# Tape_V2.net
KiCad netlist of a schematic drawn in EAGLE
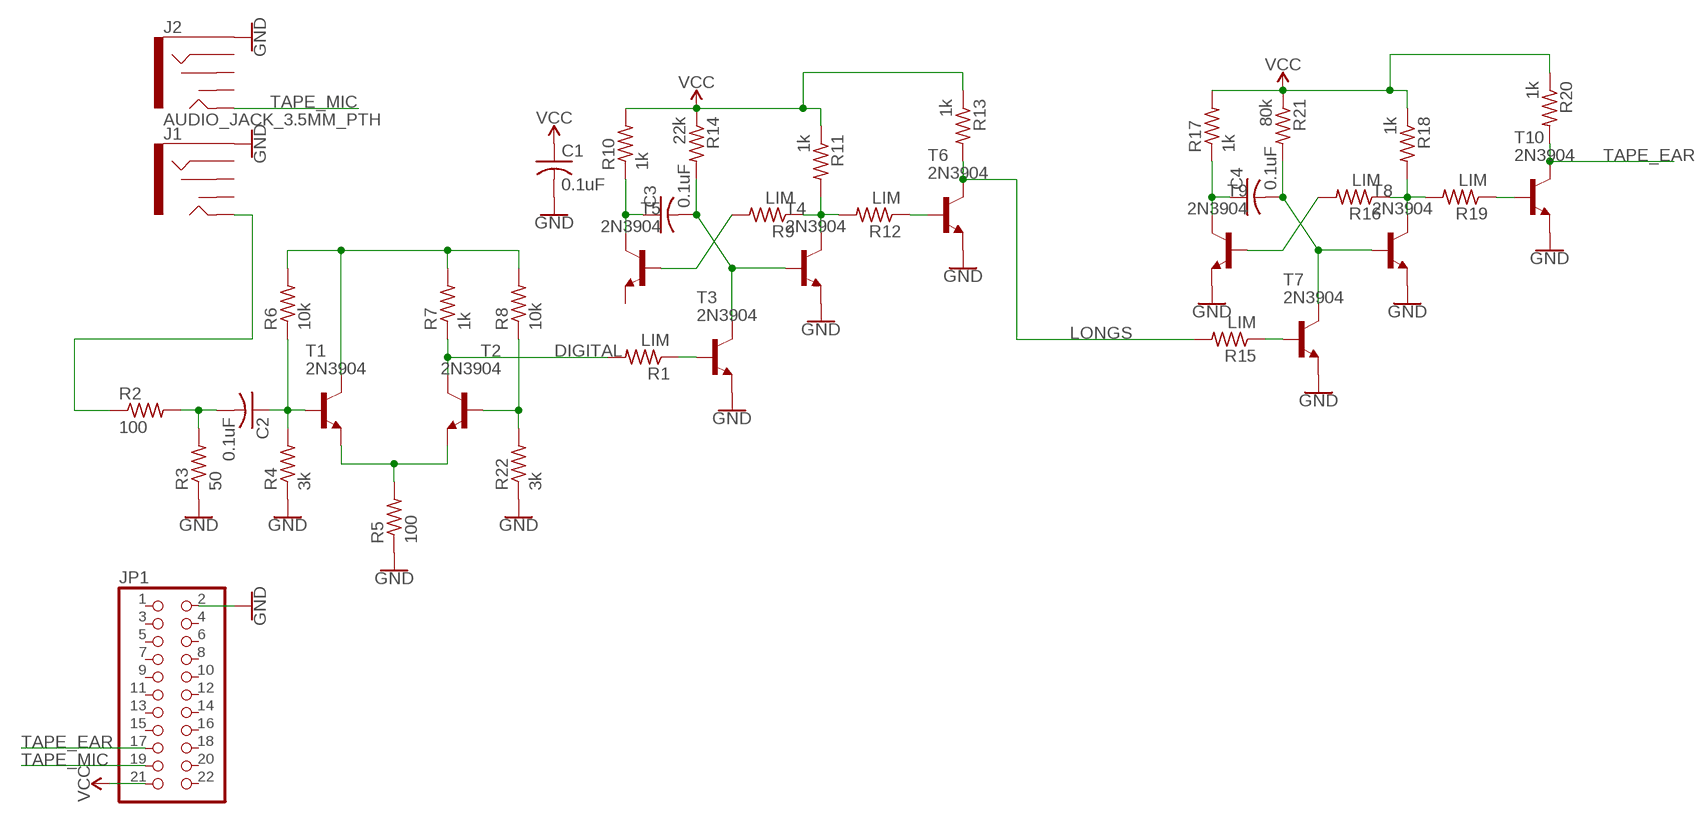
[diagram p0: schematic, sheet 1]

(export (version "E")
  (design (tool "Eeschema 10.0.6"))
  (components
    (comp (ref "C1")
      (value "0.1uF")
      (footprint "eagle-import:C025-030X050")
      (libsource (lib "eagle-import") (part "C-US025-030X050"))
    )
    (comp (ref "C2")
      (value "0.1uF")
      (footprint "eagle-import:C025-030X050")
      (libsource (lib "eagle-import") (part "C-US025-030X050"))
    )
    (comp (ref "C3")
      (value "0.1uF")
      (footprint "eagle-import:C025-030X050")
      (libsource (lib "eagle-import") (part "C-US025-030X050"))
    )
    (comp (ref "C4")
      (value "0.1uF")
      (footprint "eagle-import:C025-030X050")
      (libsource (lib "eagle-import") (part "C-US025-030X050"))
    )
    (comp (ref "J1")
      (value "AUDIO_JACK_3.5MM_PTH")
      (footprint "eagle-import:AUDIO-JACK")
      (libsource (lib "eagle-import") (part "AUDIO_JACK_3.5MM_PTH"))
    )
    (comp (ref "J2")
      (value "AUDIO_JACK_3.5MM_PTH")
      (footprint "eagle-import:AUDIO-JACK")
      (libsource (lib "eagle-import") (part "AUDIO_JACK_3.5MM_PTH"))
    )
    (comp (ref "JP1")
      (value "PINHD-2X11/90")
      (footprint "eagle-import:2X11_90")
      (libsource (lib "eagle-import") (part "PINHD-2X11/90"))
    )
    (comp (ref "R1")
      (value "LIM")
      (footprint "eagle-import:0204_7")
      (libsource (lib "eagle-import") (part "R-US_0204/7"))
    )
    (comp (ref "R2")
      (value "100")
      (footprint "eagle-import:0204_7")
      (libsource (lib "eagle-import") (part "R-US_0204/7"))
    )
    (comp (ref "R3")
      (value "50")
      (footprint "eagle-import:0204_7")
      (libsource (lib "eagle-import") (part "R-US_0204/7"))
    )
    (comp (ref "R4")
      (value "3k")
      (footprint "eagle-import:0204_7")
      (libsource (lib "eagle-import") (part "R-US_0204/7"))
    )
    (comp (ref "R5")
      (value "100")
      (footprint "eagle-import:0204_7")
      (libsource (lib "eagle-import") (part "R-US_0204/7"))
    )
    (comp (ref "R6")
      (value "10k")
      (footprint "eagle-import:0204_7")
      (libsource (lib "eagle-import") (part "R-US_0204/7"))
    )
    (comp (ref "R7")
      (value "1k")
      (footprint "eagle-import:0204_7")
      (libsource (lib "eagle-import") (part "R-US_0204/7"))
    )
    (comp (ref "R8")
      (value "10k")
      (footprint "eagle-import:0204_7")
      (libsource (lib "eagle-import") (part "R-US_0204/7"))
    )
    (comp (ref "R9")
      (value "LIM")
      (footprint "eagle-import:0204_7")
      (libsource (lib "eagle-import") (part "R-US_0204/7"))
    )
    (comp (ref "R10")
      (value "1k")
      (footprint "eagle-import:0204_7")
      (libsource (lib "eagle-import") (part "R-US_0204/7"))
    )
    (comp (ref "R11")
      (value "1k")
      (footprint "eagle-import:0204_7")
      (libsource (lib "eagle-import") (part "R-US_0204/7"))
    )
    (comp (ref "R12")
      (value "LIM")
      (footprint "eagle-import:0204_7")
      (libsource (lib "eagle-import") (part "R-US_0204/7"))
    )
    (comp (ref "R13")
      (value "1k")
      (footprint "eagle-import:0204_7")
      (libsource (lib "eagle-import") (part "R-US_0204/7"))
    )
    (comp (ref "R14")
      (value "22k")
      (footprint "eagle-import:0204_7")
      (libsource (lib "eagle-import") (part "R-US_0204/7"))
    )
    (comp (ref "R15")
      (value "LIM")
      (footprint "eagle-import:0204_7")
      (libsource (lib "eagle-import") (part "R-US_0204/7"))
    )
    (comp (ref "R16")
      (value "LIM")
      (footprint "eagle-import:0204_7")
      (libsource (lib "eagle-import") (part "R-US_0204/7"))
    )
    (comp (ref "R17")
      (value "1k")
      (footprint "eagle-import:0204_7")
      (libsource (lib "eagle-import") (part "R-US_0204/7"))
    )
    (comp (ref "R18")
      (value "1k")
      (footprint "eagle-import:0204_7")
      (libsource (lib "eagle-import") (part "R-US_0204/7"))
    )
    (comp (ref "R19")
      (value "LIM")
      (footprint "eagle-import:0204_7")
      (libsource (lib "eagle-import") (part "R-US_0204/7"))
    )
    (comp (ref "R20")
      (value "1k")
      (footprint "eagle-import:0204_7")
      (libsource (lib "eagle-import") (part "R-US_0204/7"))
    )
    (comp (ref "R21")
      (value "80k")
      (footprint "eagle-import:0204_7")
      (libsource (lib "eagle-import") (part "R-US_0204/7"))
    )
    (comp (ref "R22")
      (value "3k")
      (footprint "eagle-import:0204_7")
      (libsource (lib "eagle-import") (part "R-US_0204/7"))
    )
    (comp (ref "T1")
      (value "2N3904")
      (footprint "eagle-import:TO92")
      (libsource (lib "eagle-import") (part "2N3904"))
    )
    (comp (ref "T2")
      (value "2N3904")
      (footprint "eagle-import:TO92")
      (libsource (lib "eagle-import") (part "2N3904"))
    )
    (comp (ref "T3")
      (value "2N3904")
      (footprint "eagle-import:TO92")
      (libsource (lib "eagle-import") (part "2N3904"))
    )
    (comp (ref "T4")
      (value "2N3904")
      (footprint "eagle-import:TO92")
      (libsource (lib "eagle-import") (part "2N3904"))
    )
    (comp (ref "T5")
      (value "2N3904")
      (footprint "eagle-import:TO92")
      (libsource (lib "eagle-import") (part "2N3904"))
    )
    (comp (ref "T6")
      (value "2N3904")
      (footprint "eagle-import:TO92")
      (libsource (lib "eagle-import") (part "2N3904"))
    )
    (comp (ref "T7")
      (value "2N3904")
      (footprint "eagle-import:TO92")
      (libsource (lib "eagle-import") (part "2N3904"))
    )
    (comp (ref "T8")
      (value "2N3904")
      (footprint "eagle-import:TO92")
      (libsource (lib "eagle-import") (part "2N3904"))
    )
    (comp (ref "T9")
      (value "2N3904")
      (footprint "eagle-import:TO92")
      (libsource (lib "eagle-import") (part "2N3904"))
    )
    (comp (ref "T10")
      (value "2N3904")
      (footprint "eagle-import:TO92")
      (libsource (lib "eagle-import") (part "2N3904"))
    )
  )
  (nets
    (net (code "1") (name "/DIGITAL") (class "Default")
      (node (ref "R1") (pin "2") (pinfunction "2_2") (pintype "passive"))
      (node (ref "R7") (pin "1") (pinfunction "1_1") (pintype "passive"))
      (node (ref "T2") (pin "1") (pinfunction "C_1") (pintype "passive"))
    )
    (net (code "2") (name "/LONGS") (class "Default")
      (node (ref "R13") (pin "2") (pinfunction "2_2") (pintype "passive"))
      (node (ref "R15") (pin "2") (pinfunction "2_2") (pintype "passive"))
      (node (ref "T6") (pin "1") (pinfunction "C_1") (pintype "passive"))
    )
    (net (code "3") (name "/TAPE_EAR") (class "Default")
      (node (ref "JP1") (pin "17") (pinfunction "17_17") (pintype "passive"))
      (node (ref "R20") (pin "2") (pinfunction "2_2") (pintype "passive"))
      (node (ref "T10") (pin "1") (pinfunction "C_1") (pintype "passive"))
    )
    (net (code "4") (name "/TAPE_MIC") (class "Default")
      (node (ref "J2") (pin "TIP") (pinfunction "TIP_TIP") (pintype "bidirectional"))
      (node (ref "JP1") (pin "19") (pinfunction "19_19") (pintype "passive"))
    )
    (net (code "5") (name "GND") (class "Default")
      (node (ref "C1") (pin "2") (pinfunction "2_2") (pintype "passive"))
      (node (ref "J1") (pin "SLEEVE") (pinfunction "SLEEVE_SLEEVE") (pintype "bidirectional"))
      (node (ref "J2") (pin "SLEEVE") (pinfunction "SLEEVE_SLEEVE") (pintype "bidirectional"))
      (node (ref "JP1") (pin "2") (pinfunction "2_2") (pintype "passive"))
      (node (ref "R22") (pin "1") (pinfunction "1_1") (pintype "passive"))
      (node (ref "R3") (pin "1") (pinfunction "1_1") (pintype "passive"))
      (node (ref "R4") (pin "1") (pinfunction "1_1") (pintype "passive"))
      (node (ref "R5") (pin "1") (pinfunction "1_1") (pintype "passive"))
      (node (ref "T10") (pin "3") (pinfunction "E_3") (pintype "passive"))
      (node (ref "T3") (pin "3") (pinfunction "E_3") (pintype "passive"))
      (node (ref "T4") (pin "3") (pinfunction "E_3") (pintype "passive"))
      (node (ref "T6") (pin "3") (pinfunction "E_3") (pintype "passive"))
      (node (ref "T7") (pin "3") (pinfunction "E_3") (pintype "passive"))
      (node (ref "T8") (pin "3") (pinfunction "E_3") (pintype "passive"))
      (node (ref "T9") (pin "3") (pinfunction "E_3") (pintype "passive"))
    )
    (net (code "6") (name "Net-(C2-Pad2)") (class "Default")
      (node (ref "C2") (pin "2") (pinfunction "2_2") (pintype "passive"))
      (node (ref "R2") (pin "2") (pinfunction "2_2") (pintype "passive"))
      (node (ref "R3") (pin "2") (pinfunction "2_2") (pintype "passive"))
    )
    (net (code "7") (name "Net-(J1-PadTIP)") (class "Default")
      (node (ref "J1") (pin "TIP") (pinfunction "TIP_TIP") (pintype "bidirectional"))
      (node (ref "R2") (pin "1") (pinfunction "1_1") (pintype "passive"))
    )
    (net (code "8") (name "Net-(T1-B)") (class "Default")
      (node (ref "C2") (pin "1") (pinfunction "1_1") (pintype "passive"))
      (node (ref "R4") (pin "2") (pinfunction "2_2") (pintype "passive"))
      (node (ref "R6") (pin "1") (pinfunction "1_1") (pintype "passive"))
      (node (ref "T1") (pin "2") (pinfunction "B_2") (pintype "passive"))
    )
    (net (code "9") (name "Net-(T1-C)") (class "Default")
      (node (ref "R6") (pin "2") (pinfunction "2_2") (pintype "passive"))
      (node (ref "R7") (pin "2") (pinfunction "2_2") (pintype "passive"))
      (node (ref "R8") (pin "2") (pinfunction "2_2") (pintype "passive"))
      (node (ref "T1") (pin "1") (pinfunction "C_1") (pintype "passive"))
    )
    (net (code "10") (name "Net-(T1-E)") (class "Default")
      (node (ref "R5") (pin "2") (pinfunction "2_2") (pintype "passive"))
      (node (ref "T1") (pin "3") (pinfunction "E_3") (pintype "passive"))
      (node (ref "T2") (pin "3") (pinfunction "E_3") (pintype "passive"))
    )
    (net (code "11") (name "Net-(T2-B)") (class "Default")
      (node (ref "R22") (pin "2") (pinfunction "2_2") (pintype "passive"))
      (node (ref "R8") (pin "1") (pinfunction "1_1") (pintype "passive"))
      (node (ref "T2") (pin "2") (pinfunction "B_2") (pintype "passive"))
    )
    (net (code "12") (name "Net-(T3-B)") (class "Default")
      (node (ref "R1") (pin "1") (pinfunction "1_1") (pintype "passive"))
      (node (ref "T3") (pin "2") (pinfunction "B_2") (pintype "passive"))
    )
    (net (code "13") (name "Net-(T3-C)") (class "Default")
      (node (ref "C3") (pin "2") (pinfunction "2_2") (pintype "passive"))
      (node (ref "R14") (pin "2") (pinfunction "2_2") (pintype "passive"))
      (node (ref "T3") (pin "1") (pinfunction "C_1") (pintype "passive"))
      (node (ref "T4") (pin "2") (pinfunction "B_2") (pintype "passive"))
    )
    (net (code "14") (name "Net-(T4-C)") (class "Default")
      (node (ref "R11") (pin "2") (pinfunction "2_2") (pintype "passive"))
      (node (ref "R12") (pin "2") (pinfunction "2_2") (pintype "passive"))
      (node (ref "R9") (pin "1") (pinfunction "1_1") (pintype "passive"))
      (node (ref "T4") (pin "1") (pinfunction "C_1") (pintype "passive"))
    )
    (net (code "15") (name "Net-(T5-B)") (class "Default")
      (node (ref "R9") (pin "2") (pinfunction "2_2") (pintype "passive"))
      (node (ref "T5") (pin "2") (pinfunction "B_2") (pintype "passive"))
    )
    (net (code "16") (name "Net-(T5-C)") (class "Default")
      (node (ref "C3") (pin "1") (pinfunction "1_1") (pintype "passive"))
      (node (ref "R10") (pin "1") (pinfunction "1_1") (pintype "passive"))
      (node (ref "T5") (pin "1") (pinfunction "C_1") (pintype "passive"))
    )
    (net (code "17") (name "Net-(T6-B)") (class "Default")
      (node (ref "R12") (pin "1") (pinfunction "1_1") (pintype "passive"))
      (node (ref "T6") (pin "2") (pinfunction "B_2") (pintype "passive"))
    )
    (net (code "18") (name "Net-(T7-B)") (class "Default")
      (node (ref "R15") (pin "1") (pinfunction "1_1") (pintype "passive"))
      (node (ref "T7") (pin "2") (pinfunction "B_2") (pintype "passive"))
    )
    (net (code "19") (name "Net-(T7-C)") (class "Default")
      (node (ref "C4") (pin "2") (pinfunction "2_2") (pintype "passive"))
      (node (ref "R21") (pin "2") (pinfunction "2_2") (pintype "passive"))
      (node (ref "T7") (pin "1") (pinfunction "C_1") (pintype "passive"))
      (node (ref "T8") (pin "2") (pinfunction "B_2") (pintype "passive"))
    )
    (net (code "20") (name "Net-(T8-C)") (class "Default")
      (node (ref "R16") (pin "1") (pinfunction "1_1") (pintype "passive"))
      (node (ref "R18") (pin "2") (pinfunction "2_2") (pintype "passive"))
      (node (ref "R19") (pin "2") (pinfunction "2_2") (pintype "passive"))
      (node (ref "T8") (pin "1") (pinfunction "C_1") (pintype "passive"))
    )
    (net (code "21") (name "Net-(T9-B)") (class "Default")
      (node (ref "R16") (pin "2") (pinfunction "2_2") (pintype "passive"))
      (node (ref "T9") (pin "2") (pinfunction "B_2") (pintype "passive"))
    )
    (net (code "22") (name "Net-(T9-C)") (class "Default")
      (node (ref "C4") (pin "1") (pinfunction "1_1") (pintype "passive"))
      (node (ref "R17") (pin "1") (pinfunction "1_1") (pintype "passive"))
      (node (ref "T9") (pin "1") (pinfunction "C_1") (pintype "passive"))
    )
    (net (code "23") (name "Net-(T10-B)") (class "Default")
      (node (ref "R19") (pin "1") (pinfunction "1_1") (pintype "passive"))
      (node (ref "T10") (pin "2") (pinfunction "B_2") (pintype "passive"))
    )
    (net (code "24") (name "VCC") (class "Default")
      (node (ref "C1") (pin "1") (pinfunction "1_1") (pintype "passive"))
      (node (ref "JP1") (pin "21") (pinfunction "21_21") (pintype "passive"))
      (node (ref "R10") (pin "2") (pinfunction "2_2") (pintype "passive"))
      (node (ref "R11") (pin "1") (pinfunction "1_1") (pintype "passive"))
      (node (ref "R13") (pin "1") (pinfunction "1_1") (pintype "passive"))
      (node (ref "R14") (pin "1") (pinfunction "1_1") (pintype "passive"))
      (node (ref "R17") (pin "2") (pinfunction "2_2") (pintype "passive"))
      (node (ref "R18") (pin "1") (pinfunction "1_1") (pintype "passive"))
      (node (ref "R20") (pin "1") (pinfunction "1_1") (pintype "passive"))
      (node (ref "R21") (pin "1") (pinfunction "1_1") (pintype "passive"))
    )
    (net (code "25") (name "unconnected-(J1-PadRING)") (class "Default")
      (node (ref "J1") (pin "RING") (pinfunction "RING_RING") (pintype "bidirectional"))
    )
    (net (code "26") (name "unconnected-(J1-PadRSH)") (class "Default")
      (node (ref "J1") (pin "RSH") (pinfunction "RSH_RSH") (pintype "bidirectional"))
    )
    (net (code "27") (name "unconnected-(J1-PadTSH)") (class "Default")
      (node (ref "J1") (pin "TSH") (pinfunction "TSH_TSH") (pintype "bidirectional"))
    )
    (net (code "28") (name "unconnected-(J2-PadRING)") (class "Default")
      (node (ref "J2") (pin "RING") (pinfunction "RING_RING") (pintype "bidirectional"))
    )
    (net (code "29") (name "unconnected-(J2-PadRSH)") (class "Default")
      (node (ref "J2") (pin "RSH") (pinfunction "RSH_RSH") (pintype "bidirectional"))
    )
    (net (code "30") (name "unconnected-(J2-PadTSH)") (class "Default")
      (node (ref "J2") (pin "TSH") (pinfunction "TSH_TSH") (pintype "bidirectional"))
    )
    (net (code "31") (name "unconnected-(JP1-Pad1)") (class "Default")
      (node (ref "JP1") (pin "1") (pinfunction "1_1") (pintype "passive"))
    )
    (net (code "32") (name "unconnected-(JP1-Pad3)") (class "Default")
      (node (ref "JP1") (pin "3") (pinfunction "3_3") (pintype "passive"))
    )
    (net (code "33") (name "unconnected-(JP1-Pad4)") (class "Default")
      (node (ref "JP1") (pin "4") (pinfunction "4_4") (pintype "passive"))
    )
    (net (code "34") (name "unconnected-(JP1-Pad5)") (class "Default")
      (node (ref "JP1") (pin "5") (pinfunction "5_5") (pintype "passive"))
    )
    (net (code "35") (name "unconnected-(JP1-Pad6)") (class "Default")
      (node (ref "JP1") (pin "6") (pinfunction "6_6") (pintype "passive"))
    )
    (net (code "36") (name "unconnected-(JP1-Pad7)") (class "Default")
      (node (ref "JP1") (pin "7") (pinfunction "7_7") (pintype "passive"))
    )
    (net (code "37") (name "unconnected-(JP1-Pad8)") (class "Default")
      (node (ref "JP1") (pin "8") (pinfunction "8_8") (pintype "passive"))
    )
    (net (code "38") (name "unconnected-(JP1-Pad9)") (class "Default")
      (node (ref "JP1") (pin "9") (pinfunction "9_9") (pintype "passive"))
    )
    (net (code "39") (name "unconnected-(JP1-Pad10)") (class "Default")
      (node (ref "JP1") (pin "10") (pinfunction "10_10") (pintype "passive"))
    )
    (net (code "40") (name "unconnected-(JP1-Pad11)") (class "Default")
      (node (ref "JP1") (pin "11") (pinfunction "11_11") (pintype "passive"))
    )
    (net (code "41") (name "unconnected-(JP1-Pad12)") (class "Default")
      (node (ref "JP1") (pin "12") (pinfunction "12_12") (pintype "passive"))
    )
    (net (code "42") (name "unconnected-(JP1-Pad13)") (class "Default")
      (node (ref "JP1") (pin "13") (pinfunction "13_13") (pintype "passive"))
    )
    (net (code "43") (name "unconnected-(JP1-Pad14)") (class "Default")
      (node (ref "JP1") (pin "14") (pinfunction "14_14") (pintype "passive"))
    )
    (net (code "44") (name "unconnected-(JP1-Pad15)") (class "Default")
      (node (ref "JP1") (pin "15") (pinfunction "15_15") (pintype "passive"))
    )
    (net (code "45") (name "unconnected-(JP1-Pad16)") (class "Default")
      (node (ref "JP1") (pin "16") (pinfunction "16_16") (pintype "passive"))
    )
    (net (code "46") (name "unconnected-(JP1-Pad18)") (class "Default")
      (node (ref "JP1") (pin "18") (pinfunction "18_18") (pintype "passive"))
    )
    (net (code "47") (name "unconnected-(JP1-Pad20)") (class "Default")
      (node (ref "JP1") (pin "20") (pinfunction "20_20") (pintype "passive"))
    )
    (net (code "48") (name "unconnected-(JP1-Pad22)") (class "Default")
      (node (ref "JP1") (pin "22") (pinfunction "22_22") (pintype "passive"))
    )
    (net (code "49") (name "unconnected-(T5-E-Pad3)") (class "Default")
      (node (ref "T5") (pin "3") (pinfunction "E_3") (pintype "passive"))
    )
  )
)
